# debugger.net
KiCad netlist of a schematic drawn in Altium Designer
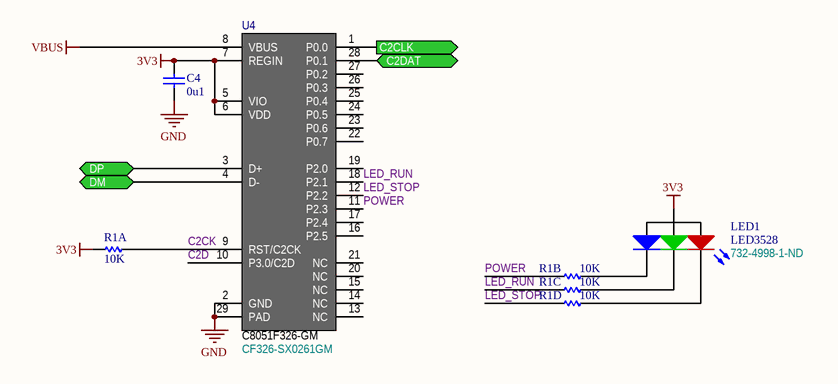
[diagram p0: debugger.SchDoc]

(export (version "E")
  (design (tool "Eeschema 10.0.6"))
  (components
    (comp (ref "C4")
      (value "0u1")
      (footprint "CAPC1005N")
      (description "Capacitor (Semiconductor SIM Model)")
      (fields (field (name "PUBLISHER") "Altium Limited"))
      (libsource (lib "Miscellaneous Devices") (part "Cap Semi"))
    )
    (comp (ref "LED1")
      (value "LED3528")
      (footprint "LED3528")
      (description "RGB LED")
      (fields
        (field (name "SUPPLIER PART NUMBER 1") "732-4998-1-ND")
        (field (name "PUBLISHER") "Altium Limited")
      )
      (libsource (lib "Miscellaneous Devices") (part "LED_RGB"))
    )
    (comp (ref "R1")
      (value "10K")
      (footprint "RESNET_8_1206")
      (description "Isolated Resistor Network - Parts")
      (fields (field (name "Comment") "Res Pack5") (field (name "PUBLISHER") "Altium Limited"))
      (libsource (lib "Miscellaneous Devices") (part "Res Pack5"))
    )
    (comp (ref "U4")
      (value "C8051F326-GM")
      (footprint "QFN50P500X500-28VAN")
      (description "IC MCU 8BIT 16KB FLASH 28QFN")
      (fields
        (field (name "MANUFACTURER") "Silicon Labs")
        (field (name "SUPPLIER PART NUMBER 1") "CF326-SX0261GM")
      )
      (libsource (lib "SiLabs 8-bit MCU") (part "C8051F326-GM"))
    )
  )
  (nets
    (net (code "1") (name "/C2CK") (class "Default")
      (node (ref "R1") (pin "8") (pinfunction "8_8") (pintype "passive"))
      (node (ref "U4") (pin "9") (pinfunction "RST/C2CK_9") (pintype "power_in"))
    )
    (net (code "2") (name "/C2CLK") (class "Default")
      (node (ref "U4") (pin "1") (pinfunction "P0.0_1") (pintype "power_in"))
    )
    (net (code "3") (name "/C2D") (class "Default")
      (node (ref "U4") (pin "10") (pinfunction "P3.0/C2D_10") (pintype "power_in"))
    )
    (net (code "4") (name "/C2DAT") (class "Default")
      (node (ref "U4") (pin "28") (pinfunction "P0.1_28") (pintype "power_in"))
    )
    (net (code "5") (name "/DM") (class "Default")
      (node (ref "U4") (pin "4") (pinfunction "D-_4") (pintype "power_in"))
    )
    (net (code "6") (name "/DP") (class "Default")
      (node (ref "U4") (pin "3") (pinfunction "D+_3") (pintype "power_in"))
    )
    (net (code "7") (name "/LED_RUN") (class "Default")
      (node (ref "R1") (pin "6") (pinfunction "6_6") (pintype "passive"))
      (node (ref "U4") (pin "18") (pinfunction "P2.1_18") (pintype "power_in"))
    )
    (net (code "8") (name "/LED_STOP") (class "Default")
      (node (ref "R1") (pin "5") (pinfunction "5_5") (pintype "passive"))
      (node (ref "U4") (pin "12") (pinfunction "P2.2_12") (pintype "power_in"))
    )
    (net (code "9") (name "/POWER") (class "Default")
      (node (ref "R1") (pin "7") (pinfunction "7_7") (pintype "passive"))
      (node (ref "U4") (pin "11") (pinfunction "P2.3_11") (pintype "power_in"))
    )
    (net (code "10") (name "3V3") (class "Default")
      (node (ref "C4") (pin "2") (pinfunction "2_2") (pintype "passive"))
      (node (ref "LED1") (pin "1") (pinfunction "A_1") (pintype "passive"))
      (node (ref "R1") (pin "1") (pinfunction "1_1") (pintype "passive"))
      (node (ref "U4") (pin "5") (pinfunction "VIO_5") (pintype "power_in"))
      (node (ref "U4") (pin "6") (pinfunction "VDD_6") (pintype "power_in"))
      (node (ref "U4") (pin "7") (pinfunction "REGIN_7") (pintype "power_in"))
    )
    (net (code "11") (name "GND") (class "Default")
      (node (ref "C4") (pin "1") (pinfunction "1_1") (pintype "passive"))
      (node (ref "U4") (pin "2") (pinfunction "GND_2") (pintype "power_in"))
      (node (ref "U4") (pin "29") (pinfunction "PAD_29") (pintype "power_in"))
    )
    (net (code "12") (name "Net-(LED1-K_B)") (class "Default")
      (node (ref "LED1") (pin "2") (pinfunction "K_B_2") (pintype "passive"))
      (node (ref "R1") (pin "2") (pinfunction "2_2") (pintype "passive"))
    )
    (net (code "13") (name "Net-(LED1-K_G)") (class "Default")
      (node (ref "LED1") (pin "4") (pinfunction "K_G_4") (pintype "passive"))
      (node (ref "R1") (pin "3") (pinfunction "3_3") (pintype "passive"))
    )
    (net (code "14") (name "Net-(LED1-K_R)") (class "Default")
      (node (ref "LED1") (pin "3") (pinfunction "K_R_3") (pintype "passive"))
      (node (ref "R1") (pin "4") (pinfunction "4_4") (pintype "passive"))
    )
    (net (code "15") (name "VBUS") (class "Default")
      (node (ref "U4") (pin "8") (pinfunction "VBUS_8") (pintype "power_in"))
    )
    (net (code "16") (name "unconnected-(U4-NC-Pad13)") (class "Default")
      (node (ref "U4") (pin "13") (pinfunction "NC_13") (pintype "power_in"))
    )
    (net (code "17") (name "unconnected-(U4-NC-Pad14)") (class "Default")
      (node (ref "U4") (pin "14") (pinfunction "NC_14") (pintype "power_in"))
    )
    (net (code "18") (name "unconnected-(U4-NC-Pad15)") (class "Default")
      (node (ref "U4") (pin "15") (pinfunction "NC_15") (pintype "power_in"))
    )
    (net (code "19") (name "unconnected-(U4-NC-Pad20)") (class "Default")
      (node (ref "U4") (pin "20") (pinfunction "NC_20") (pintype "power_in"))
    )
    (net (code "20") (name "unconnected-(U4-NC-Pad21)") (class "Default")
      (node (ref "U4") (pin "21") (pinfunction "NC_21") (pintype "power_in"))
    )
    (net (code "21") (name "unconnected-(U4-P0.2-Pad27)") (class "Default")
      (node (ref "U4") (pin "27") (pinfunction "P0.2_27") (pintype "power_in"))
    )
    (net (code "22") (name "unconnected-(U4-P0.3-Pad26)") (class "Default")
      (node (ref "U4") (pin "26") (pinfunction "P0.3_26") (pintype "power_in"))
    )
    (net (code "23") (name "unconnected-(U4-P0.4-Pad25)") (class "Default")
      (node (ref "U4") (pin "25") (pinfunction "P0.4_25") (pintype "power_in"))
    )
    (net (code "24") (name "unconnected-(U4-P0.5-Pad24)") (class "Default")
      (node (ref "U4") (pin "24") (pinfunction "P0.5_24") (pintype "power_in"))
    )
    (net (code "25") (name "unconnected-(U4-P0.6-Pad23)") (class "Default")
      (node (ref "U4") (pin "23") (pinfunction "P0.6_23") (pintype "power_in"))
    )
    (net (code "26") (name "unconnected-(U4-P0.7-Pad22)") (class "Default")
      (node (ref "U4") (pin "22") (pinfunction "P0.7_22") (pintype "power_in"))
    )
    (net (code "27") (name "unconnected-(U4-P2.0-Pad19)") (class "Default")
      (node (ref "U4") (pin "19") (pinfunction "P2.0_19") (pintype "power_in"))
    )
    (net (code "28") (name "unconnected-(U4-P2.4-Pad17)") (class "Default")
      (node (ref "U4") (pin "17") (pinfunction "P2.4_17") (pintype "power_in"))
    )
    (net (code "29") (name "unconnected-(U4-P2.5-Pad16)") (class "Default")
      (node (ref "U4") (pin "16") (pinfunction "P2.5_16") (pintype "power_in"))
    )
  )
)
